# pca20054_sheet4_power_control.net
KiCad netlist of a schematic drawn in Altium Designer
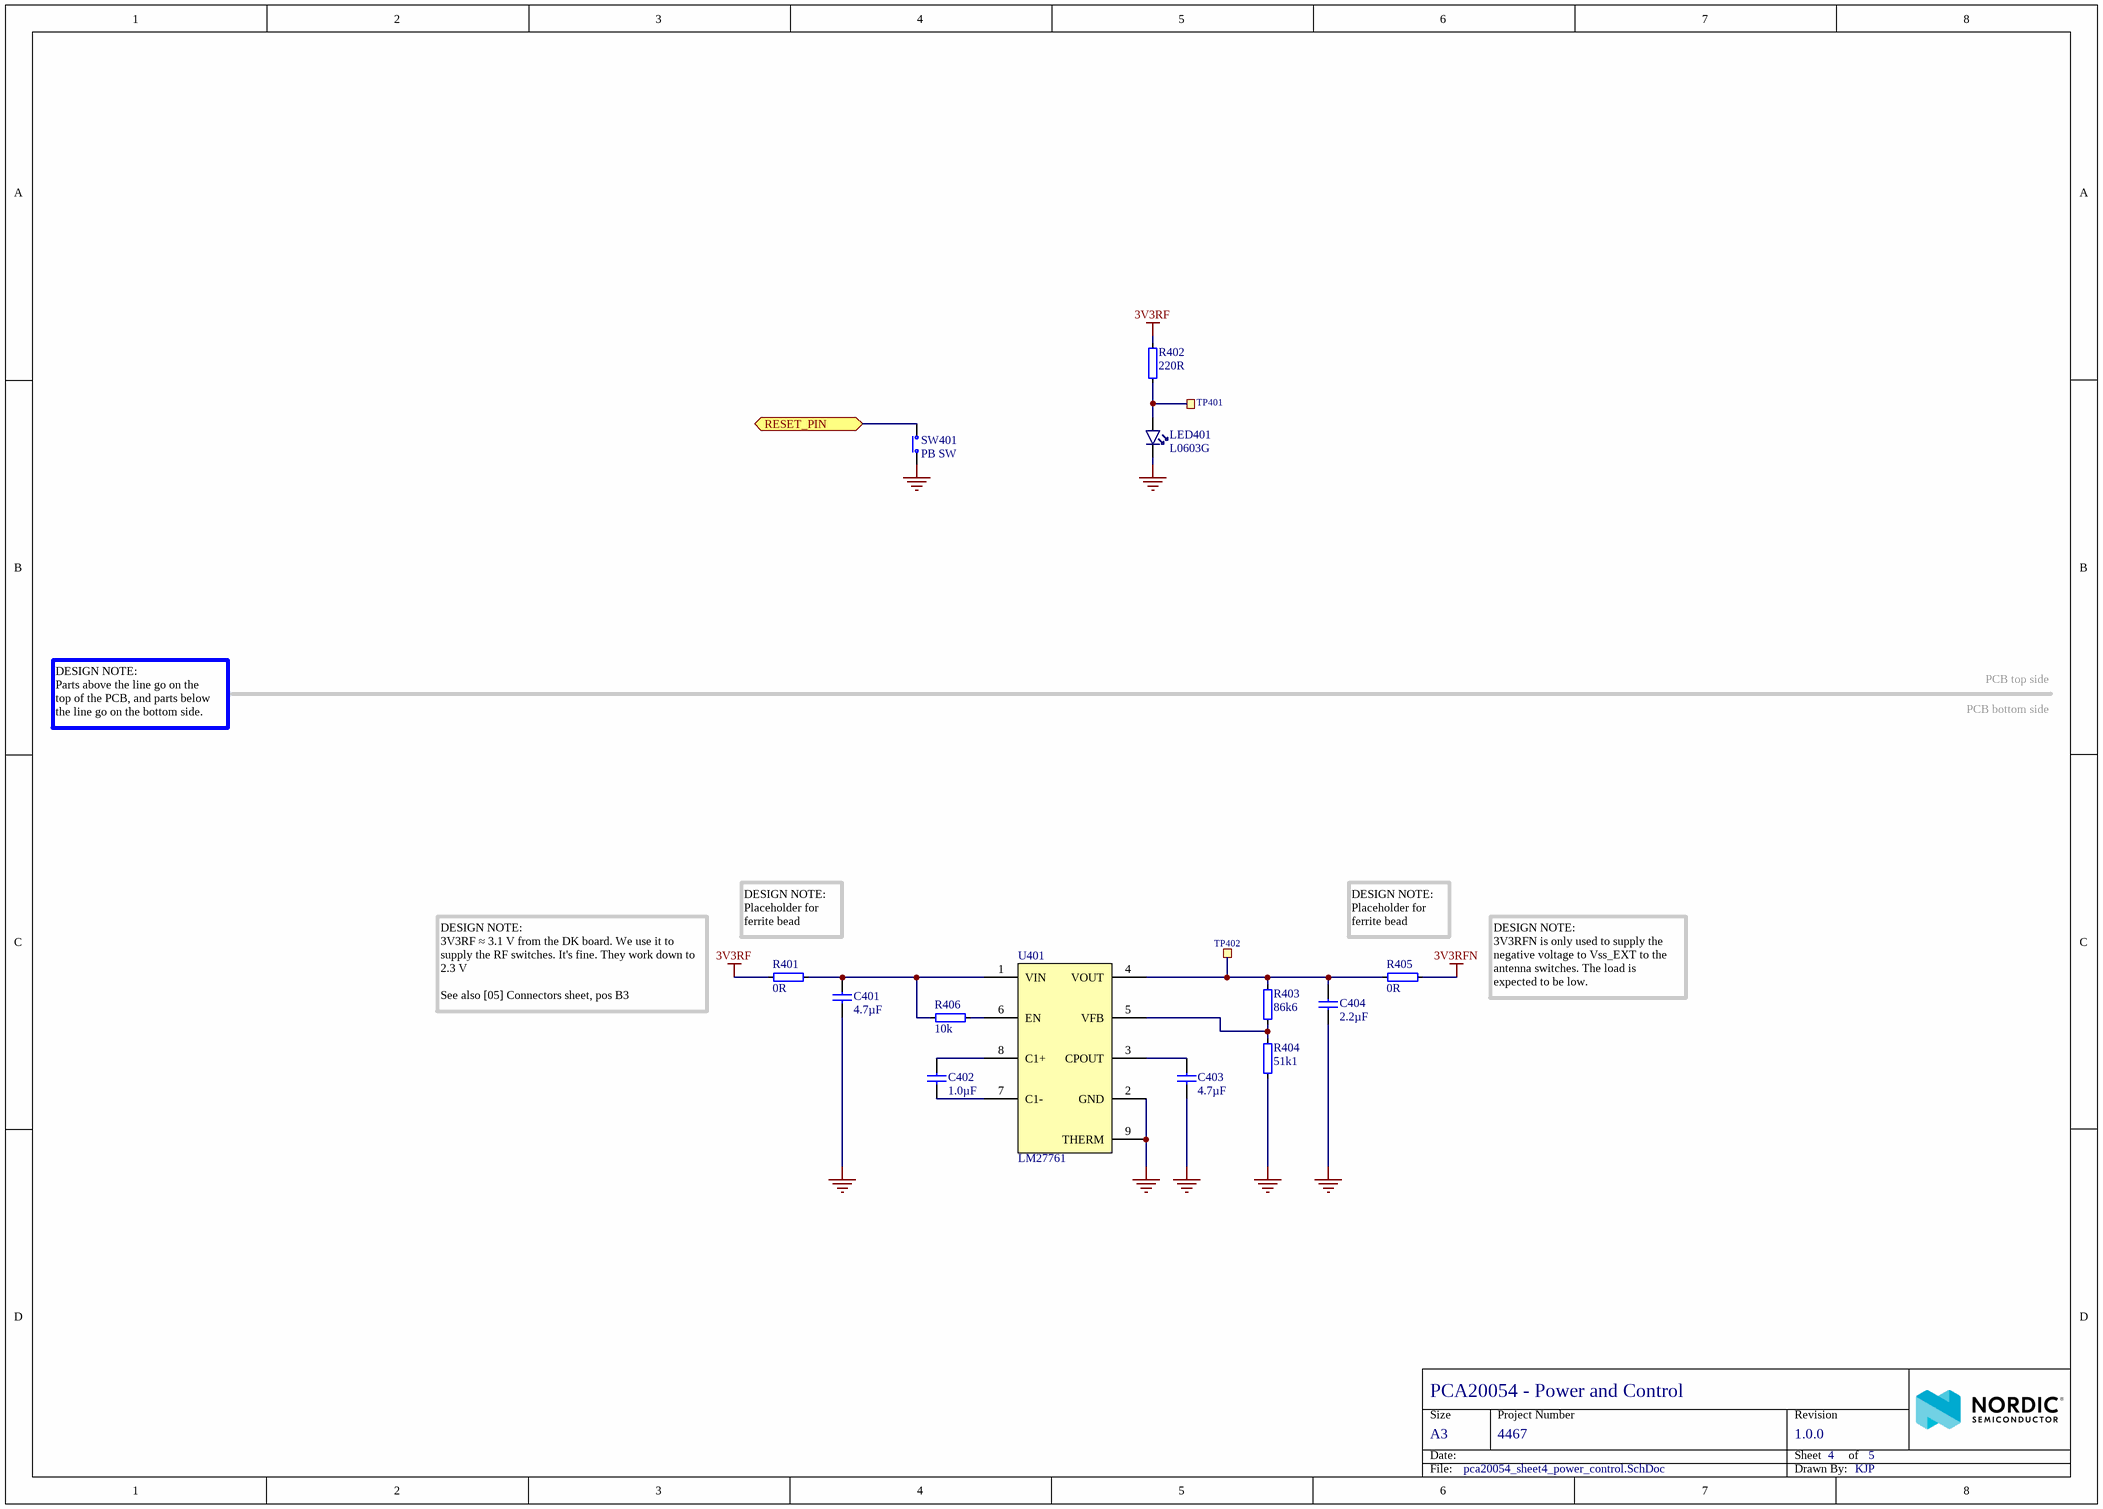
[diagram p0: pca20054_sheet4_power_control.SchDoc]

(export (version "E")
  (design (tool "Eeschema 10.0.6"))
  (components
    (comp (ref "C401")
      (value "4.7µF")
      (footprint "CAPC1608X06L")
      (description "Capacitor, X5R, ±10%")
      (fields (field (name "PART NUMBER") "C0603-4µ7") (field (name "PUBLISHER") "Nordic Semiconductor"))
      (libsource (lib "Nordic Passive DB") (part "CAP"))
    )
    (comp (ref "C402")
      (value "1.0µF")
      (footprint "CAPC1608X06L")
      (description "Capacitor, X7R, ±10%")
      (fields (field (name "PART NUMBER") "C0603-1µ0") (field (name "PUBLISHER") "Nordic Semiconductor"))
      (libsource (lib "Nordic Passive DB") (part "CAP"))
    )
    (comp (ref "C403")
      (value "4.7µF")
      (footprint "CAPC1608X06L")
      (description "Capacitor, X5R, ±10%")
      (fields (field (name "PART NUMBER") "C0603-4µ7") (field (name "PUBLISHER") "Nordic Semiconductor"))
      (libsource (lib "Nordic Passive DB") (part "CAP"))
    )
    (comp (ref "C404")
      (value "2.2µF")
      (footprint "CAPC1608X06L")
      (description "Capacitor, X7R, ±10%")
      (fields (field (name "PART NUMBER") "C0603-2µ2") (field (name "PUBLISHER") "Nordic Semiconductor"))
      (libsource (lib "Nordic Passive DB") (part "CAP"))
    )
    (comp (ref "LED401")
      (value "L0603G")
      (footprint "LED_0603_G")
      (description "LED, Green, 0603, 570nm, Vf=1.7V, 2.24..5.6mcd, - 40 to +100°C")
      (fields
        (field (name "PART NUMBER") "LG L29K Smartled Green")
        (field (name "MANUFACTURER") "Osram")
        (field (name "PUBLISHER") "Nordic Semiconductor")
      )
      (libsource (lib "Nordic Discrete DB") (part "D{colon}LED"))
    )
    (comp (ref "R401")
      (value "0R")
      (footprint "RESC1005X04L")
      (description "Resistor, ±5%, 0.063W")
      (fields (field (name "PART NUMBER") "R0402-0R") (field (name "PUBLISHER") "Nordic Semiconductor"))
      (libsource (lib "Nordic Passive DB") (part "RES"))
    )
    (comp (ref "R402")
      (value "220R")
      (footprint "RESC1005X04L")
      (description "Resistor, ±1%, 0.063W")
      (fields (field (name "PART NUMBER") "R0402-220") (field (name "PUBLISHER") "Nordic Semiconductor"))
      (libsource (lib "Nordic Passive DB") (part "RES"))
    )
    (comp (ref "R403")
      (value "86k6")
      (footprint "RESC1005X04L")
      (description "Resistor, ±1%, 0.063W")
      (fields
        (field (name "PART NUMBER") "R0402-86k6")
        (field (name "MANUFACTURER") "Panasonic")
        (field (name "PUBLISHER") "Nordic Semiconductor")
      )
      (libsource (lib "Nordic Passive DB") (part "RES"))
    )
    (comp (ref "R404")
      (value "51k1")
      (footprint "RESC1005X04L")
      (description "Resistor, ±0.1%, 0.063W")
      (fields
        (field (name "PART NUMBER") "R0402-51k1")
        (field (name "MANUFACTURER") "Panasonic")
        (field (name "PUBLISHER") "Nordic Semiconductor")
      )
      (libsource (lib "Nordic Passive DB") (part "RES"))
    )
    (comp (ref "R405")
      (value "0R")
      (footprint "RESC1005X04L")
      (description "Resistor, ±5%, 0.063W")
      (fields (field (name "PART NUMBER") "R0402-0R") (field (name "PUBLISHER") "Nordic Semiconductor"))
      (libsource (lib "Nordic Passive DB") (part "RES"))
    )
    (comp (ref "R406")
      (value "10k")
      (footprint "RESC1005X04L")
      (description "Resistor, ±1%, 0.063W")
      (fields (field (name "PART NUMBER") "R0402-10k") (field (name "PUBLISHER") "Nordic Semiconductor"))
      (libsource (lib "Nordic Passive DB") (part "RES"))
    )
    (comp (ref "SW401")
      (value "PB SW")
      (footprint "Switch-PB-6.2x6.3mm-SMD")
      (description "Tactile Switch, SPNO, SMD, 160gf, 6.2x6.3x2.5mm")
      (fields
        (field (name "PART NUMBER") "Switch-PB-6.2x6.3mm-SMD")
        (field (name "MANUFACTURER") "Dailywell")
        (field (name "PUBLISHER") "Nordic Semiconductor")
      )
      (libsource (lib "Nordic Discrete DB") (part "SW-PB"))
    )
    (comp (ref "TP401")
      (value "Ø1.0mm,SMD")
      (footprint "TP_SMD_Ø1.0mm")
      (description "1.0mm circular SMD testpad")
      (fields
        (field (name "PART NUMBER") "TP_SMD_Ø1.0MM")
        (field (name "MANUFACTURER") "Nordic Semiconductor")
        (field (name "PUBLISHER") "Nordic Semiconductor")
      )
      (libsource (lib "Nordic Passive DB") (part "TESTPAD"))
    )
    (comp (ref "TP402")
      (value "Ø1.0mm,SMD")
      (footprint "TP_SMD_Ø1.0mm")
      (description "1.0mm circular SMD testpad")
      (fields
        (field (name "PART NUMBER") "TP_SMD_Ø1.0MM")
        (field (name "MANUFACTURER") "Nordic Semiconductor")
        (field (name "PUBLISHER") "Nordic Semiconductor")
      )
      (libsource (lib "") (part "TESTPAD_1"))
    )
    (comp (ref "U401")
      (value "LM27761")
      (footprint "SON50P200X80_HS-9L")
      (description "Low-Noise, Regulated, Switched-Capacitor Voltage Inverter")
      (fields
        (field (name "MANUFACTURER") "Texas Instruments")
        (field (name "PUBLISHER") "Nordic Semiconductor")
      )
      (libsource (lib "Nordic Active DB") (part "LM27761"))
    )
  )
  (nets
    (net (code "1") (name "/RESET_PIN") (class "Default")
      (node (ref "SW401") (pin "1") (pinfunction "N.O_1") (pintype "passive"))
    )
    (net (code "2") (name "3V3RF") (class "Default")
      (node (ref "R401") (pin "1") (pinfunction "1_1") (pintype "passive"))
      (node (ref "R402") (pin "2") (pinfunction "2_2") (pintype "passive"))
    )
    (net (code "3") (name "3V3RFN") (class "Default")
      (node (ref "R405") (pin "2") (pinfunction "2_2") (pintype "passive"))
    )
    (net (code "4") (name "GND") (class "Default")
      (node (ref "C401") (pin "1") (pinfunction "1_1") (pintype "passive"))
      (node (ref "C403") (pin "1") (pinfunction "1_1") (pintype "passive"))
      (node (ref "C404") (pin "1") (pinfunction "1_1") (pintype "passive"))
      (node (ref "LED401") (pin "1") (pinfunction "C_1") (pintype "passive"))
      (node (ref "R404") (pin "1") (pinfunction "1_1") (pintype "passive"))
      (node (ref "SW401") (pin "2") (pinfunction "COM_2") (pintype "passive"))
      (node (ref "U401") (pin "2") (pinfunction "GND_2") (pintype "power_in"))
      (node (ref "U401") (pin "9") (pinfunction "THERM_9") (pintype "power_in"))
    )
    (net (code "5") (name "Net-(LED401-A)") (class "Default")
      (node (ref "LED401") (pin "2") (pinfunction "A_2") (pintype "passive"))
      (node (ref "R402") (pin "1") (pinfunction "1_1") (pintype "passive"))
      (node (ref "TP401") (pin "1") (pinfunction "1_1") (pintype "passive"))
    )
    (net (code "6") (name "Net-(U401-C1+)") (class "Default")
      (node (ref "C402") (pin "2") (pinfunction "2_2") (pintype "passive"))
      (node (ref "U401") (pin "8") (pinfunction "C1+_8") (pintype "power_in"))
    )
    (net (code "7") (name "Net-(U401-C1-)") (class "Default")
      (node (ref "C402") (pin "1") (pinfunction "1_1") (pintype "passive"))
      (node (ref "U401") (pin "7") (pinfunction "C1-_7") (pintype "power_in"))
    )
    (net (code "8") (name "Net-(U401-CPOUT)") (class "Default")
      (node (ref "C403") (pin "2") (pinfunction "2_2") (pintype "passive"))
      (node (ref "U401") (pin "3") (pinfunction "CPOUT_3") (pintype "power_in"))
    )
    (net (code "9") (name "Net-(U401-EN)") (class "Default")
      (node (ref "R406") (pin "2") (pinfunction "2_2") (pintype "passive"))
      (node (ref "U401") (pin "6") (pinfunction "EN_6") (pintype "passive"))
    )
    (net (code "10") (name "Net-(U401-VFB)") (class "Default")
      (node (ref "R403") (pin "1") (pinfunction "1_1") (pintype "passive"))
      (node (ref "R404") (pin "2") (pinfunction "2_2") (pintype "passive"))
      (node (ref "U401") (pin "5") (pinfunction "VFB_5") (pintype "power_in"))
    )
    (net (code "11") (name "Net-(U401-VIN)") (class "Default")
      (node (ref "C401") (pin "2") (pinfunction "2_2") (pintype "passive"))
      (node (ref "R401") (pin "2") (pinfunction "2_2") (pintype "passive"))
      (node (ref "R406") (pin "1") (pinfunction "1_1") (pintype "passive"))
      (node (ref "U401") (pin "1") (pinfunction "VIN_1") (pintype "power_in"))
    )
    (net (code "12") (name "Net-(U401-VOUT)") (class "Default")
      (node (ref "C404") (pin "2") (pinfunction "2_2") (pintype "passive"))
      (node (ref "R403") (pin "2") (pinfunction "2_2") (pintype "passive"))
      (node (ref "R405") (pin "1") (pinfunction "1_1") (pintype "passive"))
      (node (ref "TP402") (pin "1") (pinfunction "1_1") (pintype "passive"))
      (node (ref "U401") (pin "4") (pinfunction "VOUT_4") (pintype "power_in"))
    )
  )
)
